# Works_007_a.net
KiCad netlist of a schematic drawn in EAGLE
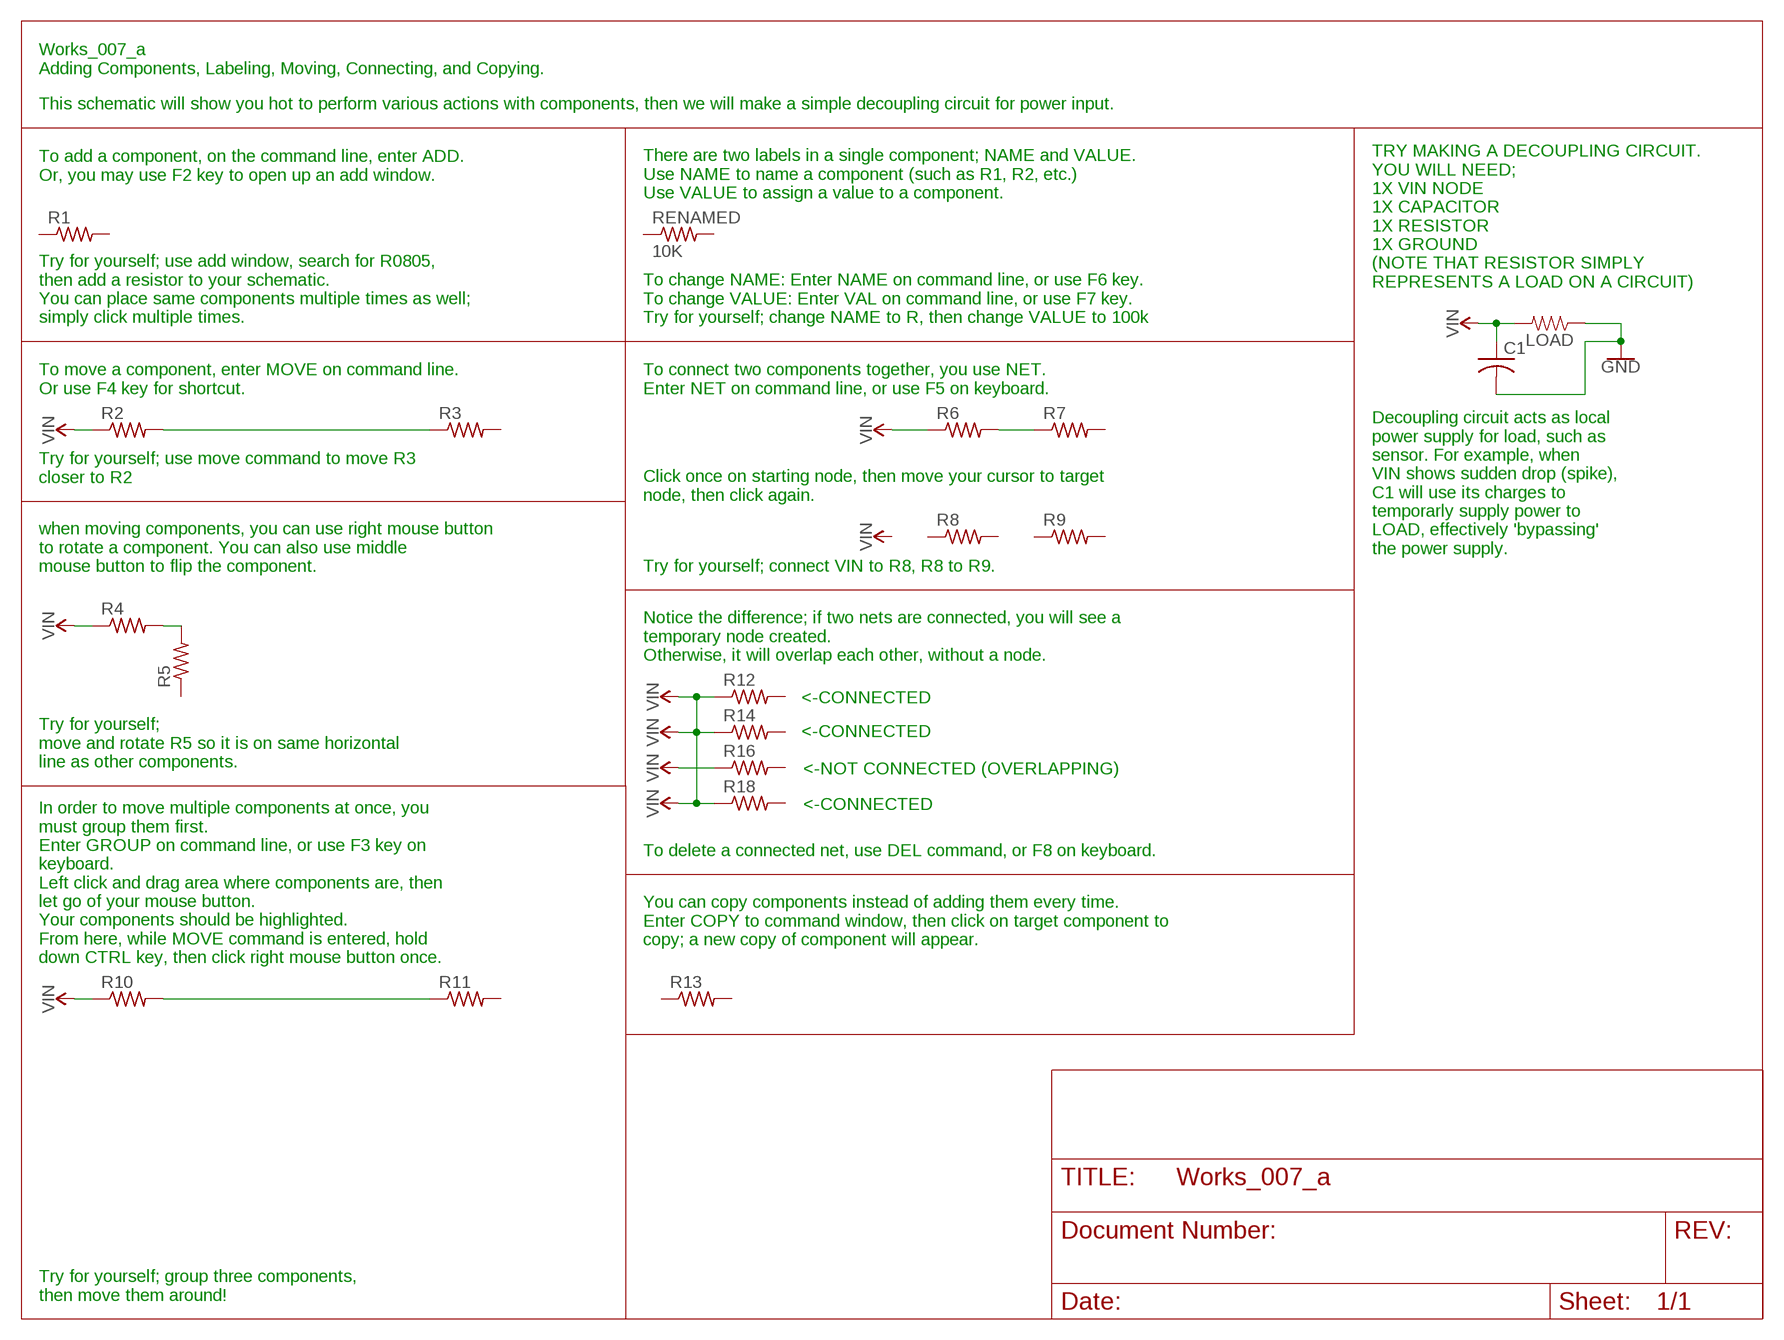
[diagram p0: schematic, sheet 1]

(export (version "E")
  (design (tool "Eeschema 10.0.6"))
  (components
    (comp (ref "C1")
      (value "C-USC0805")
      (footprint "eagle-import:C0805")
      (libsource (lib "eagle-import") (part "C-USC0805"))
    )
    (comp (ref "LOAD")
      (value "RESISTOR0805")
      (footprint "eagle-import:0805")
      (libsource (lib "eagle-import") (part "RESISTOR0805"))
    )
    (comp (ref "R1")
      (value "R-US_R0805")
      (footprint "eagle-import:R0805")
      (libsource (lib "eagle-import") (part "R-US_R0805"))
    )
    (comp (ref "R2")
      (value "R-US_R0805")
      (footprint "eagle-import:R0805")
      (libsource (lib "eagle-import") (part "R-US_R0805"))
    )
    (comp (ref "R3")
      (value "R-US_R0805")
      (footprint "eagle-import:R0805")
      (libsource (lib "eagle-import") (part "R-US_R0805"))
    )
    (comp (ref "R4")
      (value "R-US_R0805")
      (footprint "eagle-import:R0805")
      (libsource (lib "eagle-import") (part "R-US_R0805"))
    )
    (comp (ref "R5")
      (value "R-US_R0805")
      (footprint "eagle-import:R0805")
      (libsource (lib "eagle-import") (part "R-US_R0805"))
    )
    (comp (ref "R6")
      (value "R-US_R0805")
      (footprint "eagle-import:R0805")
      (libsource (lib "eagle-import") (part "R-US_R0805"))
    )
    (comp (ref "R7")
      (value "R-US_R0805")
      (footprint "eagle-import:R0805")
      (libsource (lib "eagle-import") (part "R-US_R0805"))
    )
    (comp (ref "R8")
      (value "R-US_R0805")
      (footprint "eagle-import:R0805")
      (libsource (lib "eagle-import") (part "R-US_R0805"))
    )
    (comp (ref "R9")
      (value "R-US_R0805")
      (footprint "eagle-import:R0805")
      (libsource (lib "eagle-import") (part "R-US_R0805"))
    )
    (comp (ref "R10")
      (value "R-US_R0805")
      (footprint "eagle-import:R0805")
      (libsource (lib "eagle-import") (part "R-US_R0805"))
    )
    (comp (ref "R11")
      (value "R-US_R0805")
      (footprint "eagle-import:R0805")
      (libsource (lib "eagle-import") (part "R-US_R0805"))
    )
    (comp (ref "R12")
      (value "R-US_R0805")
      (footprint "eagle-import:R0805")
      (libsource (lib "eagle-import") (part "R-US_R0805"))
    )
    (comp (ref "R13")
      (value "R-US_R0805")
      (footprint "eagle-import:R0805")
      (libsource (lib "eagle-import") (part "R-US_R0805"))
    )
    (comp (ref "R14")
      (value "R-US_R0805")
      (footprint "eagle-import:R0805")
      (libsource (lib "eagle-import") (part "R-US_R0805"))
    )
    (comp (ref "R16")
      (value "R-US_R0805")
      (footprint "eagle-import:R0805")
      (libsource (lib "eagle-import") (part "R-US_R0805"))
    )
    (comp (ref "R18")
      (value "R-US_R0805")
      (footprint "eagle-import:R0805")
      (libsource (lib "eagle-import") (part "R-US_R0805"))
    )
    (comp (ref "RENAMED")
      (value "10K")
      (footprint "eagle-import:R0805")
      (libsource (lib "eagle-import") (part "R-US_R0805"))
    )
  )
  (nets
    (net (code "1") (name "GND") (class "Default")
      (node (ref "C1") (pin "2") (pinfunction "2_2") (pintype "passive"))
      (node (ref "LOAD") (pin "1") (pinfunction "1_1") (pintype "passive"))
    )
    (net (code "2") (name "Net-(R2-Pad2)") (class "Default")
      (node (ref "R2") (pin "2") (pinfunction "2_2") (pintype "passive"))
      (node (ref "R3") (pin "1") (pinfunction "1_1") (pintype "passive"))
    )
    (net (code "3") (name "Net-(R4-Pad2)") (class "Default")
      (node (ref "R4") (pin "2") (pinfunction "2_2") (pintype "passive"))
      (node (ref "R5") (pin "2") (pinfunction "2_2") (pintype "passive"))
    )
    (net (code "4") (name "Net-(R6-Pad2)") (class "Default")
      (node (ref "R6") (pin "2") (pinfunction "2_2") (pintype "passive"))
      (node (ref "R7") (pin "1") (pinfunction "1_1") (pintype "passive"))
    )
    (net (code "5") (name "Net-(R10-Pad2)") (class "Default")
      (node (ref "R10") (pin "2") (pinfunction "2_2") (pintype "passive"))
      (node (ref "R11") (pin "1") (pinfunction "1_1") (pintype "passive"))
    )
    (net (code "6") (name "VIN") (class "Default")
      (node (ref "C1") (pin "1") (pinfunction "1_1") (pintype "passive"))
      (node (ref "LOAD") (pin "2") (pinfunction "2_2") (pintype "passive"))
      (node (ref "R10") (pin "1") (pinfunction "1_1") (pintype "passive"))
      (node (ref "R12") (pin "1") (pinfunction "1_1") (pintype "passive"))
      (node (ref "R14") (pin "1") (pinfunction "1_1") (pintype "passive"))
      (node (ref "R16") (pin "1") (pinfunction "1_1") (pintype "passive"))
      (node (ref "R18") (pin "1") (pinfunction "1_1") (pintype "passive"))
      (node (ref "R2") (pin "1") (pinfunction "1_1") (pintype "passive"))
      (node (ref "R4") (pin "1") (pinfunction "1_1") (pintype "passive"))
      (node (ref "R6") (pin "1") (pinfunction "1_1") (pintype "passive"))
    )
    (net (code "7") (name "unconnected-(R1-Pad1)") (class "Default")
      (node (ref "R1") (pin "1") (pinfunction "1_1") (pintype "passive"))
    )
    (net (code "8") (name "unconnected-(R1-Pad2)") (class "Default")
      (node (ref "R1") (pin "2") (pinfunction "2_2") (pintype "passive"))
    )
    (net (code "9") (name "unconnected-(R3-Pad2)") (class "Default")
      (node (ref "R3") (pin "2") (pinfunction "2_2") (pintype "passive"))
    )
    (net (code "10") (name "unconnected-(R5-Pad1)") (class "Default")
      (node (ref "R5") (pin "1") (pinfunction "1_1") (pintype "passive"))
    )
    (net (code "11") (name "unconnected-(R7-Pad2)") (class "Default")
      (node (ref "R7") (pin "2") (pinfunction "2_2") (pintype "passive"))
    )
    (net (code "12") (name "unconnected-(R8-Pad1)") (class "Default")
      (node (ref "R8") (pin "1") (pinfunction "1_1") (pintype "passive"))
    )
    (net (code "13") (name "unconnected-(R8-Pad2)") (class "Default")
      (node (ref "R8") (pin "2") (pinfunction "2_2") (pintype "passive"))
    )
    (net (code "14") (name "unconnected-(R9-Pad1)") (class "Default")
      (node (ref "R9") (pin "1") (pinfunction "1_1") (pintype "passive"))
    )
    (net (code "15") (name "unconnected-(R9-Pad2)") (class "Default")
      (node (ref "R9") (pin "2") (pinfunction "2_2") (pintype "passive"))
    )
    (net (code "16") (name "unconnected-(R11-Pad2)") (class "Default")
      (node (ref "R11") (pin "2") (pinfunction "2_2") (pintype "passive"))
    )
    (net (code "17") (name "unconnected-(R12-Pad2)") (class "Default")
      (node (ref "R12") (pin "2") (pinfunction "2_2") (pintype "passive"))
    )
    (net (code "18") (name "unconnected-(R13-Pad1)") (class "Default")
      (node (ref "R13") (pin "1") (pinfunction "1_1") (pintype "passive"))
    )
    (net (code "19") (name "unconnected-(R13-Pad2)") (class "Default")
      (node (ref "R13") (pin "2") (pinfunction "2_2") (pintype "passive"))
    )
    (net (code "20") (name "unconnected-(R14-Pad2)") (class "Default")
      (node (ref "R14") (pin "2") (pinfunction "2_2") (pintype "passive"))
    )
    (net (code "21") (name "unconnected-(R16-Pad2)") (class "Default")
      (node (ref "R16") (pin "2") (pinfunction "2_2") (pintype "passive"))
    )
    (net (code "22") (name "unconnected-(R18-Pad2)") (class "Default")
      (node (ref "R18") (pin "2") (pinfunction "2_2") (pintype "passive"))
    )
    (net (code "23") (name "unconnected-(RENAMED-Pad1)") (class "Default")
      (node (ref "RENAMED") (pin "1") (pinfunction "1_1") (pintype "passive"))
    )
    (net (code "24") (name "unconnected-(RENAMED-Pad2)") (class "Default")
      (node (ref "RENAMED") (pin "2") (pinfunction "2_2") (pintype "passive"))
    )
  )
)
